# 02-Interface.net
KiCad netlist of a schematic drawn in Altium Designer
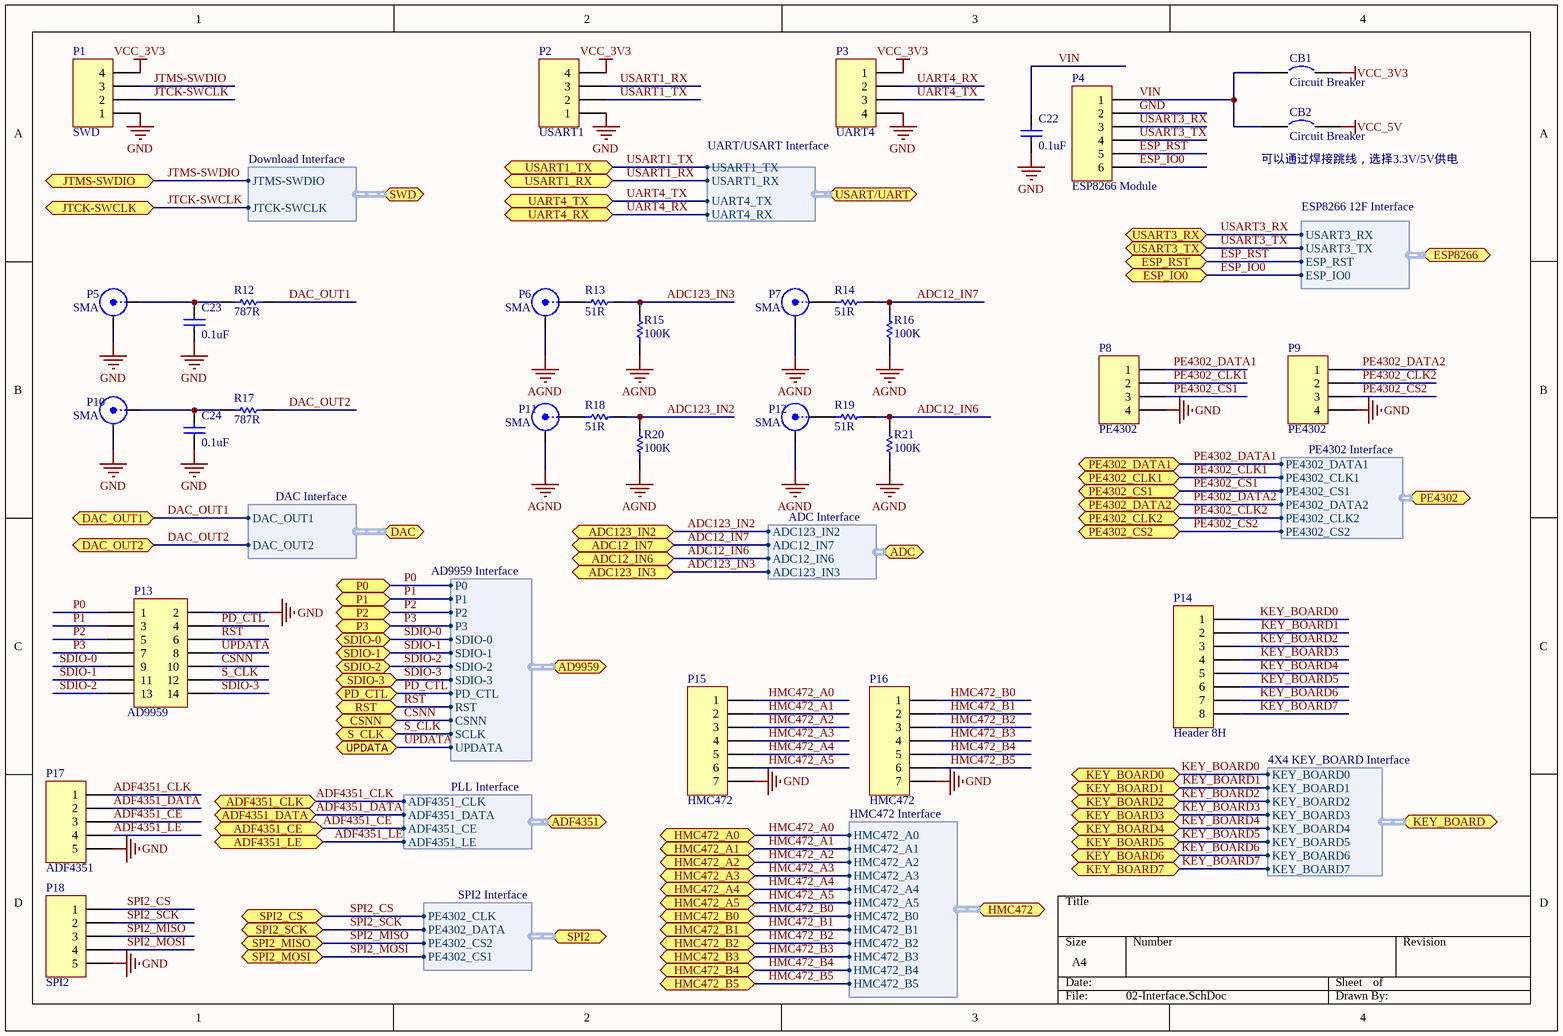
[diagram p0: 02-Interface.SchDoc]

(export (version "E")
  (design (tool "Eeschema 10.0.6"))
  (components
    (comp (ref "C22")
      (value "0.1uF")
      (footprint "0603C")
      (description "CAP CER 10000PF 100V X7R 0603")
      (fields
        (field (name "MANUFACTURER") "TDK Corporation")
        (field (name "MANUFACTURER PART NUMBER") "C1608X7R2A103K080AA")
      )
      (libsource (lib "Desiger_Schlib") (part "Cap1"))
    )
    (comp (ref "C23")
      (value "0.1uF")
      (footprint "0603C")
      (description "CAP CER 10000PF 100V X7R 0603")
      (fields
        (field (name "MANUFACTURER") "TDK Corporation")
        (field (name "MANUFACTURER PART NUMBER") "C1608X7R2A103K080AA")
      )
      (libsource (lib "Desiger_Schlib") (part "Cap1"))
    )
    (comp (ref "C24")
      (value "0.1uF")
      (footprint "0603C")
      (description "CAP CER 10000PF 100V X7R 0603")
      (fields
        (field (name "MANUFACTURER") "TDK Corporation")
        (field (name "MANUFACTURER PART NUMBER") "C1608X7R2A103K080AA")
      )
      (libsource (lib "Desiger_Schlib") (part "Cap1"))
    )
    (comp (ref "CB1")
      (value "Circuit Breaker")
      (footprint "CON20VP2R54-1X2TM")
      (fields (field (name "PUBLISHER") "Altium Limited"))
      (libsource (lib "Desiger_Schlib") (part "Circuit Breaker"))
    )
    (comp (ref "CB2")
      (value "Circuit Breaker")
      (footprint "CON20VP2R54-1X2TM")
      (fields (field (name "PUBLISHER") "Altium Limited"))
      (libsource (lib "Desiger_Schlib") (part "Circuit Breaker"))
    )
    (comp (ref "P1")
      (value "SWD")
      (footprint "1.25PWT-4P")
      (description "Header, 4-Pin")
      (fields (field (name "PUBLISHER") "Altium Limited"))
      (libsource (lib "") (part "Header 4_1"))
    )
    (comp (ref "P2")
      (value "USART1")
      (footprint "1.25PWT-4P")
      (description "Header, 4-Pin")
      (fields (field (name "PUBLISHER") "Altium Limited"))
      (libsource (lib "") (part "Header 4_1"))
    )
    (comp (ref "P3")
      (value "UART4")
      (footprint "XH_4")
      (description "Header, 4-Pin")
      (fields (field (name "PUBLISHER") "Altium Limited"))
      (libsource (lib "Miscellaneous Connectors") (part "Header 4"))
    )
    (comp (ref "P4")
      (value "ESP8266 Module")
      (footprint "CON20VP2R54-1X6TM")
      (description "Header, 6-Pin")
      (fields (field (name "PUBLISHER") "Altium Limited"))
      (libsource (lib "Miscellaneous Connectors") (part "Header 6"))
    )
    (comp (ref "P5")
      (value "SMA")
      (footprint "SMA-KE")
      (description "BNC Elbow Connector")
      (fields (field (name "PUBLISHER") "Altium Limited"))
      (libsource (lib "Miscellaneous Connectors") (part "BNC"))
    )
    (comp (ref "P6")
      (value "SMA")
      (footprint "SMA-KE")
      (description "BNC Elbow Connector")
      (fields (field (name "PUBLISHER") "Altium Limited"))
      (libsource (lib "Miscellaneous Connectors") (part "BNC"))
    )
    (comp (ref "P7")
      (value "SMA")
      (footprint "SMA-KE")
      (description "BNC Elbow Connector")
      (fields (field (name "PUBLISHER") "Altium Limited"))
      (libsource (lib "Miscellaneous Connectors") (part "BNC"))
    )
    (comp (ref "P8")
      (value "PE4302")
      (footprint "XH_4")
      (description "Header, 4-Pin")
      (fields (field (name "PUBLISHER") "Altium Limited"))
      (libsource (lib "Miscellaneous Connectors") (part "Header 4"))
    )
    (comp (ref "P9")
      (value "PE4302")
      (footprint "XH_4")
      (description "Header, 4-Pin")
      (fields (field (name "PUBLISHER") "Altium Limited"))
      (libsource (lib "Miscellaneous Connectors") (part "Header 4"))
    )
    (comp (ref "P10")
      (value "SMA")
      (footprint "SMA-KE")
      (description "BNC Elbow Connector")
      (fields (field (name "PUBLISHER") "Altium Limited"))
      (libsource (lib "Miscellaneous Connectors") (part "BNC"))
    )
    (comp (ref "P11")
      (value "SMA")
      (footprint "SMA-KE")
      (description "BNC Elbow Connector")
      (fields (field (name "PUBLISHER") "Altium Limited"))
      (libsource (lib "Miscellaneous Connectors") (part "BNC"))
    )
    (comp (ref "P12")
      (value "SMA")
      (footprint "SMA-KE")
      (description "BNC Elbow Connector")
      (fields (field (name "PUBLISHER") "Altium Limited"))
      (libsource (lib "Miscellaneous Connectors") (part "BNC"))
    )
    (comp (ref "P13")
      (value "AD9959")
      (footprint "CON20VP2R54-2X7TM-1")
      (description "Header, 7-Pin, Dual row")
      (fields (field (name "PUBLISHER") "Altium Limited"))
      (libsource (lib "Miscellaneous Connectors") (part "Header 7X2"))
    )
    (comp (ref "P14")
      (value "Header 8H")
      (footprint "XH_8")
      (description "Header, 8-Pin, Right Angle")
      (fields (field (name "PUBLISHER") "Altium Limited"))
      (libsource (lib "Miscellaneous Connectors") (part "Header 8H"))
    )
    (comp (ref "P15")
      (value "HMC472")
      (footprint "XH2.54-7P")
      (description "Header, 7-Pin")
      (fields (field (name "PUBLISHER") "Altium Limited"))
      (libsource (lib "Miscellaneous Connectors") (part "Header 7"))
    )
    (comp (ref "P16")
      (value "HMC472")
      (footprint "XH2.54-7P")
      (description "Header, 7-Pin")
      (fields (field (name "PUBLISHER") "Altium Limited"))
      (libsource (lib "Miscellaneous Connectors") (part "Header 7"))
    )
    (comp (ref "P17")
      (value "ADF4351")
      (footprint "XH_5")
      (description "Header, 5-Pin")
      (fields (field (name "PUBLISHER") "Altium Limited"))
      (libsource (lib "Miscellaneous Connectors") (part "Header 5"))
    )
    (comp (ref "P18")
      (value "SPI2")
      (footprint "XH_5")
      (description "Header, 5-Pin")
      (fields (field (name "PUBLISHER") "Altium Limited"))
      (libsource (lib "Miscellaneous Connectors") (part "Header 5"))
    )
    (comp (ref "R12")
      (value "787R")
      (footprint "0603R")
      (description "RES SMD 1K OHM 0.5% 1/16W 0603")
      (fields
        (field (name "MANUFACTURER") "Susumu")
        (field (name "MANUFACTURER PART NUMBER") "RR0816P-102-D")
      )
      (libsource (lib "Desiger_Schlib") (part "Res1"))
    )
    (comp (ref "R13")
      (value "51R")
      (footprint "0603R")
      (description "RES SMD 1K OHM 0.5% 1/16W 0603")
      (fields
        (field (name "MANUFACTURER") "Susumu")
        (field (name "MANUFACTURER PART NUMBER") "RR0816P-102-D")
      )
      (libsource (lib "Desiger_Schlib") (part "Res1"))
    )
    (comp (ref "R14")
      (value "51R")
      (footprint "0603R")
      (description "RES SMD 1K OHM 0.5% 1/16W 0603")
      (fields
        (field (name "MANUFACTURER") "Susumu")
        (field (name "MANUFACTURER PART NUMBER") "RR0816P-102-D")
      )
      (libsource (lib "Desiger_Schlib") (part "Res1"))
    )
    (comp (ref "R15")
      (value "100K")
      (footprint "0603R")
      (description "RES SMD 1K OHM 0.5% 1/16W 0603")
      (fields
        (field (name "MANUFACTURER") "Susumu")
        (field (name "MANUFACTURER PART NUMBER") "RR0816P-102-D")
      )
      (libsource (lib "Desiger_Schlib") (part "Res1"))
    )
    (comp (ref "R16")
      (value "100K")
      (footprint "0603R")
      (description "RES SMD 1K OHM 0.5% 1/16W 0603")
      (fields
        (field (name "MANUFACTURER") "Susumu")
        (field (name "MANUFACTURER PART NUMBER") "RR0816P-102-D")
      )
      (libsource (lib "Desiger_Schlib") (part "Res1"))
    )
    (comp (ref "R17")
      (value "787R")
      (footprint "0603R")
      (description "RES SMD 1K OHM 0.5% 1/16W 0603")
      (fields
        (field (name "MANUFACTURER") "Susumu")
        (field (name "MANUFACTURER PART NUMBER") "RR0816P-102-D")
      )
      (libsource (lib "Desiger_Schlib") (part "Res1"))
    )
    (comp (ref "R18")
      (value "51R")
      (footprint "0603R")
      (description "RES SMD 1K OHM 0.5% 1/16W 0603")
      (fields
        (field (name "MANUFACTURER") "Susumu")
        (field (name "MANUFACTURER PART NUMBER") "RR0816P-102-D")
      )
      (libsource (lib "Desiger_Schlib") (part "Res1"))
    )
    (comp (ref "R19")
      (value "51R")
      (footprint "0603R")
      (description "RES SMD 1K OHM 0.5% 1/16W 0603")
      (fields
        (field (name "MANUFACTURER") "Susumu")
        (field (name "MANUFACTURER PART NUMBER") "RR0816P-102-D")
      )
      (libsource (lib "Desiger_Schlib") (part "Res1"))
    )
    (comp (ref "R20")
      (value "100K")
      (footprint "0603R")
      (description "RES SMD 1K OHM 0.5% 1/16W 0603")
      (fields
        (field (name "MANUFACTURER") "Susumu")
        (field (name "MANUFACTURER PART NUMBER") "RR0816P-102-D")
      )
      (libsource (lib "Desiger_Schlib") (part "Res1"))
    )
    (comp (ref "R21")
      (value "100K")
      (footprint "0603R")
      (description "RES SMD 1K OHM 0.5% 1/16W 0603")
      (fields
        (field (name "MANUFACTURER") "Susumu")
        (field (name "MANUFACTURER PART NUMBER") "RR0816P-102-D")
      )
      (libsource (lib "Desiger_Schlib") (part "Res1"))
    )
  )
  (nets
    (net (code "15") (name "/ADC12_IN6") (class "Default")
      (node (ref "R19") (pin "1") (pinfunction "1_1") (pintype "passive"))
      (node (ref "R21") (pin "1") (pinfunction "1_1") (pintype "passive"))
    )
    (net (code "16") (name "/ADC12_IN7") (class "Default")
      (node (ref "R14") (pin "1") (pinfunction "1_1") (pintype "passive"))
      (node (ref "R16") (pin "1") (pinfunction "1_1") (pintype "passive"))
    )
    (net (code "17") (name "/ADC123_IN2") (class "Default")
      (node (ref "R18") (pin "1") (pinfunction "1_1") (pintype "passive"))
      (node (ref "R20") (pin "1") (pinfunction "1_1") (pintype "passive"))
    )
    (net (code "18") (name "/ADC123_IN3") (class "Default")
      (node (ref "R13") (pin "1") (pinfunction "1_1") (pintype "passive"))
      (node (ref "R15") (pin "1") (pinfunction "1_1") (pintype "passive"))
    )
    (net (code "19") (name "/ADF4351_CE") (class "Default")
      (node (ref "P17") (pin "3") (pinfunction "3_3") (pintype "passive"))
    )
    (net (code "20") (name "/ADF4351_CLK") (class "Default")
      (node (ref "P17") (pin "1") (pinfunction "1_1") (pintype "passive"))
    )
    (net (code "21") (name "/ADF4351_DATA") (class "Default")
      (node (ref "P17") (pin "2") (pinfunction "2_2") (pintype "passive"))
    )
    (net (code "22") (name "/ADF4351_LE") (class "Default")
      (node (ref "P17") (pin "4") (pinfunction "4_4") (pintype "passive"))
    )
    (net (code "23") (name "/CSNN") (class "Default")
      (node (ref "P13") (pin "10") (pinfunction "10_10") (pintype "passive"))
    )
    (net (code "24") (name "/DAC_OUT1") (class "Default")
      (node (ref "R12") (pin "1") (pinfunction "1_1") (pintype "passive"))
    )
    (net (code "25") (name "/DAC_OUT2") (class "Default")
      (node (ref "R17") (pin "1") (pinfunction "1_1") (pintype "passive"))
    )
    (net (code "26") (name "/ESP_IO0") (class "Default")
      (node (ref "P4") (pin "6") (pinfunction "6_6") (pintype "passive"))
    )
    (net (code "27") (name "/ESP_RST") (class "Default")
      (node (ref "P4") (pin "5") (pinfunction "5_5") (pintype "passive"))
    )
    (net (code "28") (name "/HMC472_A0") (class "Default")
      (node (ref "P15") (pin "1") (pinfunction "1_1") (pintype "passive"))
    )
    (net (code "29") (name "/HMC472_A1") (class "Default")
      (node (ref "P15") (pin "2") (pinfunction "2_2") (pintype "passive"))
    )
    (net (code "30") (name "/HMC472_A2") (class "Default")
      (node (ref "P15") (pin "3") (pinfunction "3_3") (pintype "passive"))
    )
    (net (code "31") (name "/HMC472_A3") (class "Default")
      (node (ref "P15") (pin "4") (pinfunction "4_4") (pintype "passive"))
    )
    (net (code "32") (name "/HMC472_A4") (class "Default")
      (node (ref "P15") (pin "5") (pinfunction "5_5") (pintype "passive"))
    )
    (net (code "33") (name "/HMC472_A5") (class "Default")
      (node (ref "P15") (pin "6") (pinfunction "6_6") (pintype "passive"))
    )
    (net (code "34") (name "/HMC472_B0") (class "Default")
      (node (ref "P16") (pin "1") (pinfunction "1_1") (pintype "passive"))
    )
    (net (code "35") (name "/HMC472_B1") (class "Default")
      (node (ref "P16") (pin "2") (pinfunction "2_2") (pintype "passive"))
    )
    (net (code "36") (name "/HMC472_B2") (class "Default")
      (node (ref "P16") (pin "3") (pinfunction "3_3") (pintype "passive"))
    )
    (net (code "37") (name "/HMC472_B3") (class "Default")
      (node (ref "P16") (pin "4") (pinfunction "4_4") (pintype "passive"))
    )
    (net (code "38") (name "/HMC472_B4") (class "Default")
      (node (ref "P16") (pin "5") (pinfunction "5_5") (pintype "passive"))
    )
    (net (code "39") (name "/HMC472_B5") (class "Default")
      (node (ref "P16") (pin "6") (pinfunction "6_6") (pintype "passive"))
    )
    (net (code "40") (name "/JTCK-SWCLK") (class "Default")
      (node (ref "P1") (pin "2") (pinfunction "2_2") (pintype "passive"))
    )
    (net (code "41") (name "/JTMS-SWDIO") (class "Default")
      (node (ref "P1") (pin "3") (pinfunction "3_3") (pintype "passive"))
    )
    (net (code "42") (name "/KEY_BOARD0") (class "Default")
      (node (ref "P14") (pin "1") (pinfunction "1_1") (pintype "passive"))
    )
    (net (code "43") (name "/KEY_BOARD1") (class "Default")
      (node (ref "P14") (pin "2") (pinfunction "2_2") (pintype "passive"))
    )
    (net (code "44") (name "/KEY_BOARD2") (class "Default")
      (node (ref "P14") (pin "3") (pinfunction "3_3") (pintype "passive"))
    )
    (net (code "45") (name "/KEY_BOARD3") (class "Default")
      (node (ref "P14") (pin "4") (pinfunction "4_4") (pintype "passive"))
    )
    (net (code "46") (name "/KEY_BOARD4") (class "Default")
      (node (ref "P14") (pin "5") (pinfunction "5_5") (pintype "passive"))
    )
    (net (code "47") (name "/KEY_BOARD5") (class "Default")
      (node (ref "P14") (pin "6") (pinfunction "6_6") (pintype "passive"))
    )
    (net (code "48") (name "/KEY_BOARD6") (class "Default")
      (node (ref "P14") (pin "7") (pinfunction "7_7") (pintype "passive"))
    )
    (net (code "49") (name "/KEY_BOARD7") (class "Default")
      (node (ref "P14") (pin "8") (pinfunction "8_8") (pintype "passive"))
    )
    (net (code "50") (name "/P0") (class "Default")
      (node (ref "P13") (pin "1") (pinfunction "1_1") (pintype "passive"))
    )
    (net (code "51") (name "/P1") (class "Default")
      (node (ref "P13") (pin "3") (pinfunction "3_3") (pintype "passive"))
    )
    (net (code "52") (name "/P2") (class "Default")
      (node (ref "P13") (pin "5") (pinfunction "5_5") (pintype "passive"))
    )
    (net (code "53") (name "/P3") (class "Default")
      (node (ref "P13") (pin "7") (pinfunction "7_7") (pintype "passive"))
    )
    (net (code "54") (name "/PD_CTL") (class "Default")
      (node (ref "P13") (pin "4") (pinfunction "4_4") (pintype "passive"))
    )
    (net (code "55") (name "/PE4302_CLK1") (class "Default")
      (node (ref "P8") (pin "2") (pinfunction "2_2") (pintype "passive"))
    )
    (net (code "56") (name "/PE4302_CLK2") (class "Default")
      (node (ref "P9") (pin "2") (pinfunction "2_2") (pintype "passive"))
    )
    (net (code "57") (name "/PE4302_CS1") (class "Default")
      (node (ref "P8") (pin "3") (pinfunction "3_3") (pintype "passive"))
    )
    (net (code "58") (name "/PE4302_CS2") (class "Default")
      (node (ref "P9") (pin "3") (pinfunction "3_3") (pintype "passive"))
    )
    (net (code "59") (name "/PE4302_DATA1") (class "Default")
      (node (ref "P8") (pin "1") (pinfunction "1_1") (pintype "passive"))
    )
    (net (code "60") (name "/PE4302_DATA2") (class "Default")
      (node (ref "P9") (pin "1") (pinfunction "1_1") (pintype "passive"))
    )
    (net (code "61") (name "/RST") (class "Default")
      (node (ref "P13") (pin "6") (pinfunction "6_6") (pintype "passive"))
    )
    (net (code "62") (name "/SDIO-0") (class "Default")
      (node (ref "P13") (pin "9") (pinfunction "9_9") (pintype "passive"))
    )
    (net (code "63") (name "/SDIO-1") (class "Default")
      (node (ref "P13") (pin "11") (pinfunction "11_11") (pintype "passive"))
    )
    (net (code "64") (name "/SDIO-2") (class "Default")
      (node (ref "P13") (pin "13") (pinfunction "13_13") (pintype "passive"))
    )
    (net (code "65") (name "/SDIO-3") (class "Default")
      (node (ref "P13") (pin "14") (pinfunction "14_14") (pintype "passive"))
    )
    (net (code "66") (name "/SPI2_CS") (class "Default")
      (node (ref "P18") (pin "1") (pinfunction "1_1") (pintype "passive"))
    )
    (net (code "67") (name "/SPI2_MISO") (class "Default")
      (node (ref "P18") (pin "3") (pinfunction "3_3") (pintype "passive"))
    )
    (net (code "68") (name "/SPI2_MOSI") (class "Default")
      (node (ref "P18") (pin "4") (pinfunction "4_4") (pintype "passive"))
    )
    (net (code "69") (name "/SPI2_SCK") (class "Default")
      (node (ref "P18") (pin "2") (pinfunction "2_2") (pintype "passive"))
    )
    (net (code "70") (name "/S_CLK") (class "Default")
      (node (ref "P13") (pin "12") (pinfunction "12_12") (pintype "passive"))
    )
    (net (code "71") (name "/UART4_RX") (class "Default")
      (node (ref "P3") (pin "2") (pinfunction "2_2") (pintype "passive"))
    )
    (net (code "72") (name "/UART4_TX") (class "Default")
      (node (ref "P3") (pin "3") (pinfunction "3_3") (pintype "passive"))
    )
    (net (code "73") (name "/UPDATA") (class "Default")
      (node (ref "P13") (pin "8") (pinfunction "8_8") (pintype "passive"))
    )
    (net (code "74") (name "/USART1_RX") (class "Default")
      (node (ref "P2") (pin "3") (pinfunction "3_3") (pintype "passive"))
    )
    (net (code "75") (name "/USART1_TX") (class "Default")
      (node (ref "P2") (pin "2") (pinfunction "2_2") (pintype "passive"))
    )
    (net (code "76") (name "/USART3_RX") (class "Default")
      (node (ref "P4") (pin "3") (pinfunction "3_3") (pintype "passive"))
    )
    (net (code "77") (name "/USART3_TX") (class "Default")
      (node (ref "P4") (pin "4") (pinfunction "4_4") (pintype "passive"))
    )
    (net (code "78") (name "/VIN") (class "Default")
      (node (ref "C22") (pin "1") (pinfunction "1_1") (pintype "passive"))
      (node (ref "CB1") (pin "1") (pinfunction "1_1") (pintype "passive"))
      (node (ref "CB2") (pin "1") (pinfunction "1_1") (pintype "passive"))
      (node (ref "P4") (pin "1") (pinfunction "1_1") (pintype "passive"))
    )
    (net (code "90") (name "AGND") (class "Default")
      (node (ref "P11") (pin "2") (pinfunction "Y_2") (pintype "passive"))
      (node (ref "P12") (pin "2") (pinfunction "Y_2") (pintype "passive"))
      (node (ref "P6") (pin "2") (pinfunction "Y_2") (pintype "passive"))
      (node (ref "P7") (pin "2") (pinfunction "Y_2") (pintype "passive"))
      (node (ref "R15") (pin "2") (pinfunction "2_2") (pintype "passive"))
      (node (ref "R16") (pin "2") (pinfunction "2_2") (pintype "passive"))
      (node (ref "R20") (pin "2") (pinfunction "2_2") (pintype "passive"))
      (node (ref "R21") (pin "2") (pinfunction "2_2") (pintype "passive"))
    )
    (net (code "91") (name "GND") (class "Default")
      (node (ref "C22") (pin "2") (pinfunction "2_2") (pintype "passive"))
      (node (ref "C23") (pin "2") (pinfunction "2_2") (pintype "passive"))
      (node (ref "C24") (pin "2") (pinfunction "2_2") (pintype "passive"))
      (node (ref "P1") (pin "1") (pinfunction "1_1") (pintype "passive"))
      (node (ref "P10") (pin "2") (pinfunction "Y_2") (pintype "passive"))
      (node (ref "P13") (pin "2") (pinfunction "2_2") (pintype "passive"))
      (node (ref "P15") (pin "7") (pinfunction "7_7") (pintype "passive"))
      (node (ref "P16") (pin "7") (pinfunction "7_7") (pintype "passive"))
      (node (ref "P17") (pin "5") (pinfunction "5_5") (pintype "passive"))
      (node (ref "P18") (pin "5") (pinfunction "5_5") (pintype "passive"))
      (node (ref "P2") (pin "1") (pinfunction "1_1") (pintype "passive"))
      (node (ref "P3") (pin "4") (pinfunction "4_4") (pintype "passive"))
      (node (ref "P4") (pin "2") (pinfunction "2_2") (pintype "passive"))
      (node (ref "P5") (pin "2") (pinfunction "Y_2") (pintype "passive"))
      (node (ref "P8") (pin "4") (pinfunction "4_4") (pintype "passive"))
      (node (ref "P9") (pin "4") (pinfunction "4_4") (pintype "passive"))
    )
    (net (code "92") (name "Net-(P5-X)") (class "Default")
      (node (ref "C23") (pin "1") (pinfunction "1_1") (pintype "passive"))
      (node (ref "P5") (pin "1") (pinfunction "X_1") (pintype "passive"))
      (node (ref "R12") (pin "2") (pinfunction "2_2") (pintype "passive"))
    )
    (net (code "93") (name "Net-(P6-X)") (class "Default")
      (node (ref "P6") (pin "1") (pinfunction "X_1") (pintype "passive"))
      (node (ref "R13") (pin "2") (pinfunction "2_2") (pintype "passive"))
    )
    (net (code "94") (name "Net-(P7-X)") (class "Default")
      (node (ref "P7") (pin "1") (pinfunction "X_1") (pintype "passive"))
      (node (ref "R14") (pin "2") (pinfunction "2_2") (pintype "passive"))
    )
    (net (code "95") (name "Net-(P10-X)") (class "Default")
      (node (ref "C24") (pin "1") (pinfunction "1_1") (pintype "passive"))
      (node (ref "P10") (pin "1") (pinfunction "X_1") (pintype "passive"))
      (node (ref "R17") (pin "2") (pinfunction "2_2") (pintype "passive"))
    )
    (net (code "96") (name "Net-(P11-X)") (class "Default")
      (node (ref "P11") (pin "1") (pinfunction "X_1") (pintype "passive"))
      (node (ref "R18") (pin "2") (pinfunction "2_2") (pintype "passive"))
    )
    (net (code "97") (name "Net-(P12-X)") (class "Default")
      (node (ref "P12") (pin "1") (pinfunction "X_1") (pintype "passive"))
      (node (ref "R19") (pin "2") (pinfunction "2_2") (pintype "passive"))
    )
    (net (code "98") (name "VCC_3V3") (class "Default")
      (node (ref "CB1") (pin "2") (pinfunction "2_2") (pintype "passive"))
      (node (ref "P1") (pin "4") (pinfunction "4_4") (pintype "passive"))
      (node (ref "P2") (pin "4") (pinfunction "4_4") (pintype "passive"))
      (node (ref "P3") (pin "1") (pinfunction "1_1") (pintype "passive"))
    )
    (net (code "99") (name "VCC_5V") (class "Default")
      (node (ref "CB2") (pin "2") (pinfunction "2_2") (pintype "passive"))
    )
  )
)
